# FPGA_CFG.net
KiCad netlist of a schematic drawn in Altium Designer
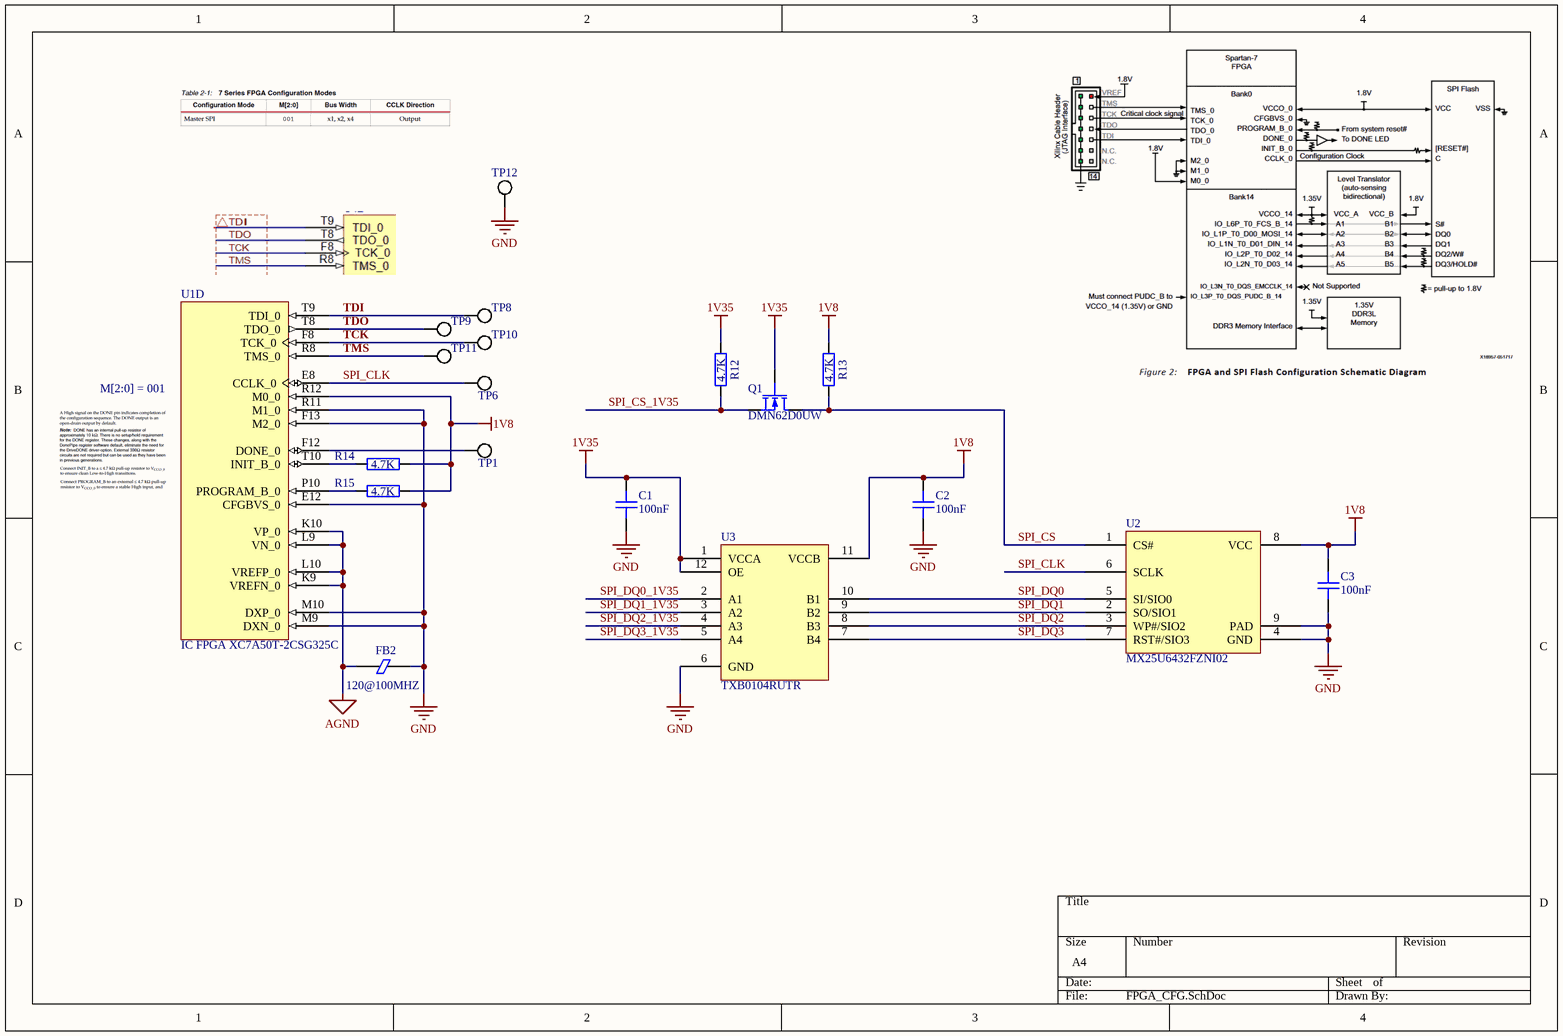
[diagram p0: FPGA_CFG.SchDoc]

(export (version "E")
  (design (tool "Eeschema 10.0.6"))
  (components
    (comp (ref "C1")
      (value "100nF")
      (footprint "GEN_C_0402")
      (fields
        (field (name "HOUSE PART NUMBER") "C-100nF-0402-002")
        (field (name "MANUFACTURER") "Murata")
        (field (name "MANUFACTURER PART NUMBER") "GCM155R71C104KA55D")
      )
      (libsource (lib "DSO") (part "CAP 100nF 16V X7R 0402"))
    )
    (comp (ref "C2")
      (value "100nF")
      (footprint "GEN_C_0402")
      (fields
        (field (name "HOUSE PART NUMBER") "C-100nF-0402-002")
        (field (name "MANUFACTURER") "Murata")
        (field (name "MANUFACTURER PART NUMBER") "GCM155R71C104KA55D")
      )
      (libsource (lib "DSO") (part "CAP 100nF 16V X7R 0402"))
    )
    (comp (ref "C3")
      (value "100nF")
      (footprint "GEN_C_0402")
      (fields
        (field (name "HOUSE PART NUMBER") "C-100nF-0402-002")
        (field (name "MANUFACTURER") "Murata")
        (field (name "MANUFACTURER PART NUMBER") "GCM155R71C104KA55D")
      )
      (libsource (lib "DSO") (part "CAP 100nF 16V X7R 0402"))
    )
    (comp (ref "FB2")
      (value "120@100MHZ")
      (footprint "GEN_R_0402")
      (fields (field (name "HOUSE PART NUMBER") "BLM15PX121SN1D") (field (name "MANUFACTURER") "Murata"))
      (libsource (lib "DSO") (part "FERRITE BEAD 120 OHM 0402"))
    )
    (comp (ref "Q1")
      (value "DMN62D0UW")
      (footprint "GEN_SOT_323")
      (fields (field (name "HOUSE PART NUMBER") "DMN62D0UW-7") (field (name "MANUFACTURER") "Diodes"))
      (libsource (lib "DSO") (part "NMOS DMN62D0UW"))
    )
    (comp (ref "R12")
      (value "4.7K")
      (footprint "GEN_R_0201")
      (fields
        (field (name "TOLERANCE") "1%")
        (field (name "HOUSE PART NUMBER") "R-4.7K-0201-1%-001")
        (field (name "MANUFACTURER") "Yageo")
      )
      (libsource (lib "") (part "RES 4.7K OHM 1% 1/20W 0201_1"))
    )
    (comp (ref "R13")
      (value "4.7K")
      (footprint "GEN_R_0201")
      (fields
        (field (name "TOLERANCE") "1%")
        (field (name "HOUSE PART NUMBER") "R-4.7K-0201-1%-001")
        (field (name "MANUFACTURER") "Yageo")
      )
      (libsource (lib "") (part "RES 4.7K OHM 1% 1/20W 0201_1"))
    )
    (comp (ref "R14")
      (value "4.7K")
      (footprint "GEN_R_0201")
      (fields
        (field (name "TOLERANCE") "1%")
        (field (name "HOUSE PART NUMBER") "R-4.7K-0201-1%-001")
        (field (name "MANUFACTURER") "Yageo")
      )
      (libsource (lib "DSO") (part "RES 4.7K OHM 1% 1/20W 0201"))
    )
    (comp (ref "R15")
      (value "4.7K")
      (footprint "GEN_R_0201")
      (fields
        (field (name "TOLERANCE") "1%")
        (field (name "HOUSE PART NUMBER") "R-4.7K-0201-1%-001")
        (field (name "MANUFACTURER") "Yageo")
      )
      (libsource (lib "DSO") (part "RES 4.7K OHM 1% 1/20W 0201"))
    )
    (comp (ref "TP1") (value "PCB") (footprint "GEN_TP_PCB") (libsource (lib "DSO") (part "TP PCB 1mm")))
    (comp (ref "TP6") (value "PCB") (footprint "GEN_TP_PCB") (libsource (lib "DSO") (part "TP PCB 1mm")))
    (comp (ref "TP8") (value "PCB") (footprint "GEN_TP_PCB") (libsource (lib "DSO") (part "TP PCB 1mm")))
    (comp (ref "TP9") (value "PCB") (footprint "GEN_TP_PCB") (libsource (lib "DSO") (part "TP PCB 1mm")))
    (comp (ref "TP10") (value "PCB") (footprint "GEN_TP_PCB") (libsource (lib "DSO") (part "TP PCB 1mm")))
    (comp (ref "TP11") (value "PCB") (footprint "GEN_TP_PCB") (libsource (lib "DSO") (part "TP PCB 1mm")))
    (comp (ref "TP12") (value "PCB") (footprint "GEN_TP_PCB") (libsource (lib "DSO") (part "TP PCB 1mm")))
    (comp (ref "U1")
      (value "IC FPGA XC7A50T-2CSG325C")
      (footprint "XILINX_XC7A50T-2CSG325C")
      (description "Artix-7 FPGA, 150 User I/Os, 4 GTP, 324-Ball BGA, Speed Grade 2, Commercial Grade, Pb-Free")
      (fields (field (name "MANUFACTURER") "Xilinx") (field (name "HOUSE PART NUMBER") "XC7A50T-2CSG325C"))
      (libsource (lib "DSO") (part "IC FPGA XC7A50T-2CSG325C"))
    )
    (comp (ref "U2")
      (value "MX25U6432FZNI02")
      (footprint "MX_WSON8")
      (fields (field (name "MANUFACTURER") "Macronix"))
      (libsource (lib "DSO") (part "IC FLASH MX25U6432FZNI02"))
    )
    (comp (ref "U3")
      (value "TXB0104RUTR")
      (footprint "TI_UQFN_RUT0012A")
      (fields (field (name "MANUFACTURER") "Texas Instruments"))
      (libsource (lib "DSO") (part "IC TRNSLTR TXB0104RUTR"))
    )
  )
  (nets
    (net (code "1") (name "/SPI_CLK") (class "Default")
      (node (ref "TP6") (pin "1") (pinfunction "1_1") (pintype "passive"))
      (node (ref "U1") (pin "E8") (pinfunction "CCLK_0_E8") (pintype "bidirectional"))
      (node (ref "U2") (pin "6") (pinfunction "SCLK_6") (pintype "passive"))
    )
    (net (code "2") (name "/SPI_CS") (class "Default")
      (node (ref "Q1") (pin "1") (pinfunction "D_1") (pintype "passive"))
      (node (ref "R13") (pin "1") (pinfunction "1_1") (pintype "passive"))
      (node (ref "U2") (pin "1") (pinfunction "CS#_1") (pintype "passive"))
    )
    (net (code "3") (name "/SPI_CS_1V35") (class "Default")
      (node (ref "Q1") (pin "3") (pinfunction "S_3") (pintype "passive"))
      (node (ref "R12") (pin "1") (pinfunction "1_1") (pintype "passive"))
    )
    (net (code "4") (name "/SPI_DQ0") (class "Default")
      (node (ref "U2") (pin "5") (pinfunction "SI/SIO0_5") (pintype "passive"))
      (node (ref "U3") (pin "10") (pinfunction "B1_10") (pintype "passive"))
    )
    (net (code "5") (name "/SPI_DQ0_1V35") (class "Default")
      (node (ref "U3") (pin "2") (pinfunction "A1_2") (pintype "passive"))
    )
    (net (code "6") (name "/SPI_DQ1") (class "Default")
      (node (ref "U2") (pin "2") (pinfunction "SO/SIO1_2") (pintype "passive"))
      (node (ref "U3") (pin "9") (pinfunction "B2_9") (pintype "passive"))
    )
    (net (code "7") (name "/SPI_DQ1_1V35") (class "Default")
      (node (ref "U3") (pin "3") (pinfunction "A2_3") (pintype "passive"))
    )
    (net (code "8") (name "/SPI_DQ2") (class "Default")
      (node (ref "U2") (pin "3") (pinfunction "WP#/SIO2_3") (pintype "passive"))
      (node (ref "U3") (pin "8") (pinfunction "B3_8") (pintype "passive"))
    )
    (net (code "9") (name "/SPI_DQ2_1V35") (class "Default")
      (node (ref "U3") (pin "4") (pinfunction "A3_4") (pintype "passive"))
    )
    (net (code "10") (name "/SPI_DQ3") (class "Default")
      (node (ref "U2") (pin "7") (pinfunction "RST#/SIO3_7") (pintype "passive"))
      (node (ref "U3") (pin "7") (pinfunction "B4_7") (pintype "passive"))
    )
    (net (code "11") (name "/SPI_DQ3_1V35") (class "Default")
      (node (ref "U3") (pin "5") (pinfunction "A4_5") (pintype "passive"))
    )
    (net (code "12") (name "/TCK") (class "Default")
      (node (ref "TP10") (pin "1") (pinfunction "1_1") (pintype "passive"))
      (node (ref "U1") (pin "F8") (pinfunction "TCK_0_F8") (pintype "input"))
    )
    (net (code "13") (name "/TDI") (class "Default")
      (node (ref "TP8") (pin "1") (pinfunction "1_1") (pintype "passive"))
      (node (ref "U1") (pin "T9") (pinfunction "TDI_0_T9") (pintype "input"))
    )
    (net (code "14") (name "/TDO") (class "Default")
      (node (ref "TP9") (pin "1") (pinfunction "1_1") (pintype "passive"))
      (node (ref "U1") (pin "T8") (pinfunction "TDO_0_T8") (pintype "output"))
    )
    (net (code "15") (name "/TMS") (class "Default")
      (node (ref "TP11") (pin "1") (pinfunction "1_1") (pintype "passive"))
      (node (ref "U1") (pin "R8") (pinfunction "TMS_0_R8") (pintype "input"))
    )
    (net (code "16") (name "1V8") (class "Default")
      (node (ref "C2") (pin "1") (pinfunction "1_1") (pintype "passive"))
      (node (ref "C3") (pin "1") (pinfunction "1_1") (pintype "passive"))
      (node (ref "R13") (pin "2") (pinfunction "2_2") (pintype "passive"))
      (node (ref "R14") (pin "2") (pinfunction "2_2") (pintype "passive"))
      (node (ref "R15") (pin "2") (pinfunction "2_2") (pintype "passive"))
      (node (ref "U1") (pin "R12") (pinfunction "M0_0_R12") (pintype "input"))
      (node (ref "U2") (pin "8") (pinfunction "VCC_8") (pintype "passive"))
      (node (ref "U3") (pin "11") (pinfunction "VCCB_11") (pintype "passive"))
    )
    (net (code "17") (name "1V35") (class "Default")
      (node (ref "C1") (pin "1") (pinfunction "1_1") (pintype "passive"))
      (node (ref "Q1") (pin "2") (pinfunction "G_2") (pintype "passive"))
      (node (ref "R12") (pin "2") (pinfunction "2_2") (pintype "passive"))
      (node (ref "U3") (pin "1") (pinfunction "VCCA_1") (pintype "passive"))
      (node (ref "U3") (pin "12") (pinfunction "OE_12") (pintype "passive"))
    )
    (net (code "18") (name "AGND") (class "Default")
      (node (ref "FB2") (pin "1") (pinfunction "1_1") (pintype "passive"))
      (node (ref "U1") (pin "K10") (pinfunction "VP_0_K10") (pintype "input"))
      (node (ref "U1") (pin "K9") (pinfunction "VREFN_0_K9") (pintype "input"))
      (node (ref "U1") (pin "L10") (pinfunction "VREFP_0_L10") (pintype "input"))
      (node (ref "U1") (pin "L9") (pinfunction "VN_0_L9") (pintype "input"))
    )
    (net (code "19") (name "GND") (class "Default")
      (node (ref "C1") (pin "2") (pinfunction "2_2") (pintype "passive"))
      (node (ref "C2") (pin "2") (pinfunction "2_2") (pintype "passive"))
      (node (ref "C3") (pin "2") (pinfunction "2_2") (pintype "passive"))
      (node (ref "FB2") (pin "2") (pinfunction "2_2") (pintype "passive"))
      (node (ref "TP12") (pin "1") (pinfunction "1_1") (pintype "passive"))
      (node (ref "U1") (pin "E12") (pinfunction "CFGBVS_0_E12") (pintype "input"))
      (node (ref "U1") (pin "F13") (pinfunction "M2_0_F13") (pintype "input"))
      (node (ref "U1") (pin "M10") (pinfunction "DXP_0_M10") (pintype "input"))
      (node (ref "U1") (pin "M9") (pinfunction "DXN_0_M9") (pintype "input"))
      (node (ref "U1") (pin "R11") (pinfunction "M1_0_R11") (pintype "input"))
      (node (ref "U2") (pin "4") (pinfunction "GND_4") (pintype "passive"))
      (node (ref "U2") (pin "9") (pinfunction "PAD_9") (pintype "passive"))
      (node (ref "U3") (pin "6") (pinfunction "GND_6") (pintype "passive"))
    )
    (net (code "20") (name "Net-(U1D-DONE_0)") (class "Default")
      (node (ref "TP1") (pin "1") (pinfunction "1_1") (pintype "passive"))
      (node (ref "U1") (pin "F12") (pinfunction "DONE_0_F12") (pintype "bidirectional"))
    )
    (net (code "21") (name "Net-(U1D-INIT_B_0)") (class "Default")
      (node (ref "R14") (pin "1") (pinfunction "1_1") (pintype "passive"))
      (node (ref "U1") (pin "T10") (pinfunction "INIT_B_0_T10") (pintype "bidirectional"))
    )
    (net (code "22") (name "Net-(U1D-PROGRAM_B_0)") (class "Default")
      (node (ref "R15") (pin "1") (pinfunction "1_1") (pintype "passive"))
      (node (ref "U1") (pin "P10") (pinfunction "PROGRAM_B_0_P10") (pintype "input"))
    )
  )
)
